# Schematic.net
KiCad netlist of a schematic drawn in EasyEDA
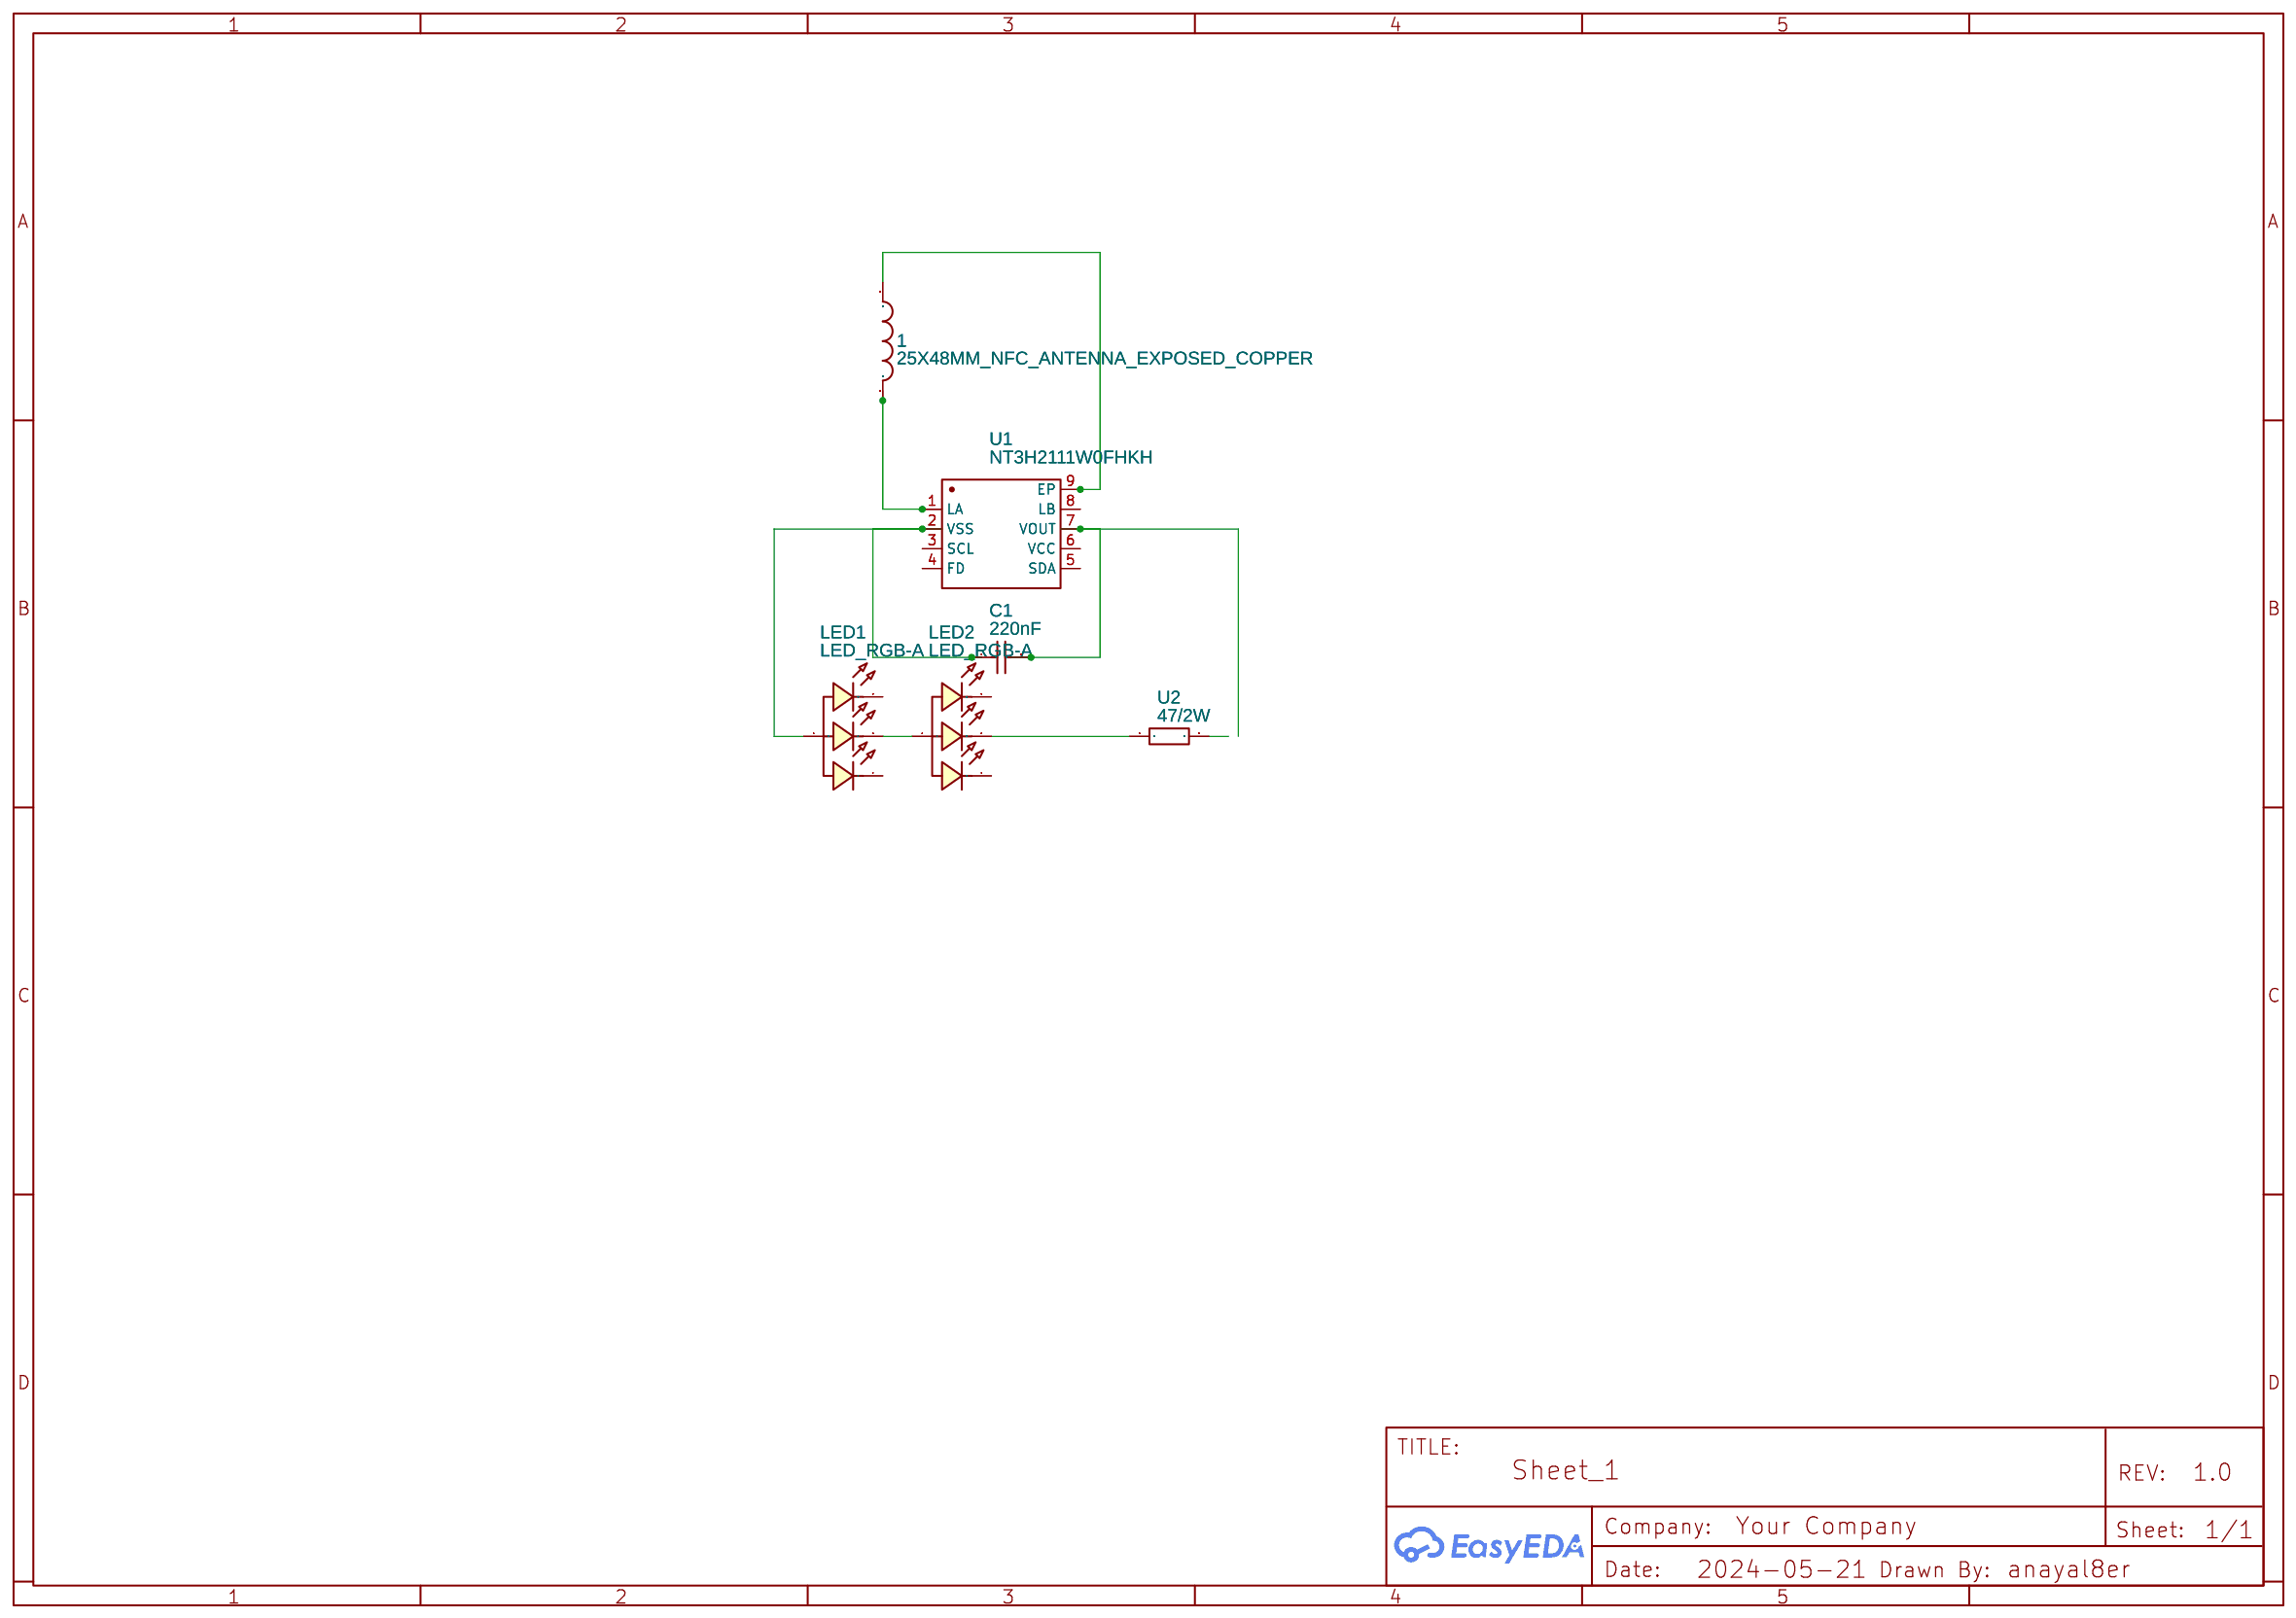
[diagram p0: schematic sheet]

(export (version "E")
  (design (tool "Eeschema 10.0.6"))
  (components
    (comp (ref "1")
      (value "25X48MM_NFC_ANTENNA_EXPOSED_COPPER")
      (libsource (lib "") (part "25X48MM_NFC_ANTENNA_EXPOSED_COPPER"))
    )
    (comp (ref "C1")
      (value "220nF")
      (fields
        (field (name "Manufacturer Part") "CL21B224KBFNNNE")
        (field (name "Manufacturer") "SAMSUNG(三星)")
      )
      (libsource (lib "") (part "CL21B224KBFNNNE"))
    )
    (comp (ref "LED1")
      (value "LED_RGB-A")
      (fields (field (name "Manufacturer Part") "LED_RGB红蓝双色"))
      (libsource (lib "") (part "LED_RGB-A"))
    )
    (comp (ref "LED2")
      (value "LED_RGB-A")
      (fields (field (name "Manufacturer Part") "LED_RGB红蓝双色"))
      (libsource (lib "") (part "LED_RGB-A"))
    )
    (comp (ref "U1")
      (value "NT3H2111W0FHKH")
      (fields (field (name "Manufacturer") "NXP(恩智浦)"))
      (libsource (lib "") (part "NT3H2111W0FHKH"))
    )
    (comp (ref "U2") (value "47/2W") (libsource (lib "") (part "47/2W")))
  )
  (nets
    (net (code "1") (name "Net-(LED1-Pad2)") (class "Default")
      (node (ref "LED1") (pin "2") (pinfunction "2_2") (pintype "unspecified"))
      (node (ref "LED2") (pin "1") (pinfunction "1_1") (pintype "unspecified"))
    )
    (net (code "2") (name "Net-(LED2-Pad2)") (class "Default")
      (node (ref "LED2") (pin "2") (pinfunction "2_2") (pintype "unspecified"))
      (node (ref "U2") (pin "1") (pinfunction "1_1") (pintype "unspecified"))
    )
    (net (code "3") (name "Net-(U1-EP)") (class "Default")
      (node (ref "1") (pin "P$1") (pinfunction "P$1_P$1") (pintype "bidirectional"))
      (node (ref "U1") (pin "9") (pinfunction "EP_9") (pintype "unspecified"))
    )
    (net (code "4") (name "Net-(U1-LA)") (class "Default")
      (node (ref "1") (pin "P$2") (pinfunction "P$2_P$2") (pintype "bidirectional"))
      (node (ref "U1") (pin "1") (pinfunction "LA_1") (pintype "unspecified"))
    )
    (net (code "5") (name "Net-(U1-VOUT)") (class "Default")
      (node (ref "C1") (pin "2") (pinfunction "2_2") (pintype "input"))
      (node (ref "U1") (pin "7") (pinfunction "VOUT_7") (pintype "unspecified"))
    )
    (net (code "6") (name "Net-(U1-VSS)") (class "Default")
      (node (ref "C1") (pin "1") (pinfunction "1_1") (pintype "input"))
      (node (ref "LED1") (pin "1") (pinfunction "1_1") (pintype "unspecified"))
      (node (ref "U1") (pin "2") (pinfunction "VSS_2") (pintype "unspecified"))
    )
    (net (code "7") (name "unconnected-(LED1-Pad3)") (class "Default")
      (node (ref "LED1") (pin "3") (pinfunction "3_3") (pintype "unspecified"))
    )
    (net (code "8") (name "unconnected-(LED1-Pad4)") (class "Default")
      (node (ref "LED1") (pin "4") (pinfunction "4_4") (pintype "unspecified"))
    )
    (net (code "9") (name "unconnected-(LED2-Pad3)") (class "Default")
      (node (ref "LED2") (pin "3") (pinfunction "3_3") (pintype "unspecified"))
    )
    (net (code "10") (name "unconnected-(LED2-Pad4)") (class "Default")
      (node (ref "LED2") (pin "4") (pinfunction "4_4") (pintype "unspecified"))
    )
    (net (code "11") (name "unconnected-(U1-FD-Pad4)") (class "Default")
      (node (ref "U1") (pin "4") (pinfunction "FD_4") (pintype "unspecified"))
    )
    (net (code "12") (name "unconnected-(U1-LB-Pad8)") (class "Default")
      (node (ref "U1") (pin "8") (pinfunction "LB_8") (pintype "unspecified"))
    )
    (net (code "13") (name "unconnected-(U1-SCL-Pad3)") (class "Default")
      (node (ref "U1") (pin "3") (pinfunction "SCL_3") (pintype "unspecified"))
    )
    (net (code "14") (name "unconnected-(U1-SDA-Pad5)") (class "Default")
      (node (ref "U1") (pin "5") (pinfunction "SDA_5") (pintype "unspecified"))
    )
    (net (code "15") (name "unconnected-(U1-VCC-Pad6)") (class "Default")
      (node (ref "U1") (pin "6") (pinfunction "VCC_6") (pintype "unspecified"))
    )
    (net (code "16") (name "unconnected-(U2-Pad2)") (class "Default")
      (node (ref "U2") (pin "2") (pinfunction "2_2") (pintype "unspecified"))
    )
  )
)
